# piccaloSchematic.net
KiCad netlist of a schematic drawn in Altium Designer
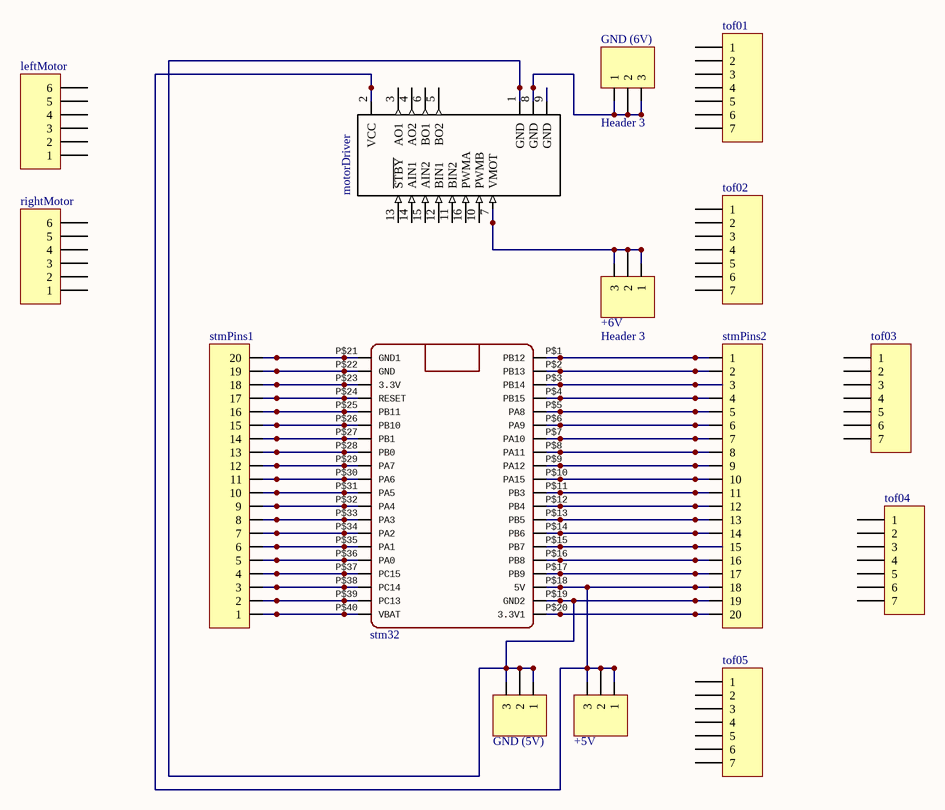
[diagram p0: piccaloSchematic.SchDoc]

(export (version "E")
  (design (tool "Eeschema 10.0.6"))
  (components
    (comp (ref "+5V")
      (value "Header 3")
      (footprint "HDR1X3")
      (description "Header, 3-Pin")
      (fields (field (name "PUBLISHER") "Altium Limited"))
      (libsource (lib "Miscellaneous Connectors") (part "Header 3"))
    )
    (comp (ref "+6V")
      (value "Header 3")
      (footprint "HDR1X3")
      (description "Header, 3-Pin")
      (fields (field (name "PUBLISHER") "Altium Limited"))
      (libsource (lib "Miscellaneous Connectors") (part "Header 3"))
    )
    (comp (ref "GND (5V)")
      (value "Header 3")
      (footprint "HDR1X3")
      (description "Header, 3-Pin")
      (fields (field (name "PUBLISHER") "Altium Limited"))
      (libsource (lib "Miscellaneous Connectors") (part "Header 3"))
    )
    (comp (ref "GND (6V)")
      (value "Header 3")
      (footprint "HDR1X3")
      (description "Header, 3-Pin")
      (fields (field (name "PUBLISHER") "Altium Limited"))
      (libsource (lib "") (part "Header 3_1"))
    )
    (comp (ref "leftMotor")
      (value "Header 6")
      (footprint "HDR1X6")
      (description "Header, 6-Pin")
      (fields (field (name "PUBLISHER") "Altium Limited"))
      (libsource (lib "Miscellaneous Connectors") (part "Header 6"))
    )
    (comp (ref "motorDriver")
      (value "POLOLU-713")
      (footprint "*SHIELD_POLOLU-713")
      (description "DC-motor driver; IC: TB6612FNG; 100kHz; 1A; Uin mot: 4.5")
      (fields (field (name "MF") "Pololu"))
      (libsource (lib "POLOLU-713") (part "POLOLU-713"))
    )
    (comp (ref "rightMotor")
      (value "Header 6")
      (footprint "HDR1X6")
      (description "Header, 6-Pin")
      (fields (field (name "PUBLISHER") "Altium Limited"))
      (libsource (lib "Miscellaneous Connectors") (part "Header 6"))
    )
    (comp (ref "stm32")
      (value "BLUE_PILLADVANCED")
      (footprint "BLUE_PILL_ADV")
      (libsource (lib "BluePill") (part "BLUE_PILLADVANCED"))
    )
    (comp (ref "stmPins1")
      (value "Header 20")
      (footprint "HDR1X20")
      (description "Header, 20-Pin")
      (fields (field (name "PUBLISHER") "Altium Limited"))
      (libsource (lib "") (part "Header 20_1"))
    )
    (comp (ref "stmPins2")
      (value "Header 20")
      (footprint "HDR1X20")
      (description "Header, 20-Pin")
      (fields (field (name "PUBLISHER") "Altium Limited"))
      (libsource (lib "Miscellaneous Connectors") (part "Header 20"))
    )
    (comp (ref "tof01")
      (value "Header 7")
      (footprint "HDR1X7")
      (description "Header, 7-Pin")
      (fields (field (name "PUBLISHER") "Altium Limited"))
      (libsource (lib "Miscellaneous Connectors") (part "Header 7"))
    )
    (comp (ref "tof02")
      (value "Header 7")
      (footprint "HDR1X7")
      (description "Header, 7-Pin")
      (fields (field (name "PUBLISHER") "Altium Limited"))
      (libsource (lib "Miscellaneous Connectors") (part "Header 7"))
    )
    (comp (ref "tof03")
      (value "Header 7")
      (footprint "HDR1X7")
      (description "Header, 7-Pin")
      (fields (field (name "PUBLISHER") "Altium Limited"))
      (libsource (lib "Miscellaneous Connectors") (part "Header 7"))
    )
    (comp (ref "tof04")
      (value "Header 7")
      (footprint "HDR1X7")
      (description "Header, 7-Pin")
      (fields (field (name "PUBLISHER") "Altium Limited"))
      (libsource (lib "Miscellaneous Connectors") (part "Header 7"))
    )
    (comp (ref "tof05")
      (value "Header 7")
      (footprint "HDR1X7")
      (description "Header, 7-Pin")
      (fields (field (name "PUBLISHER") "Altium Limited"))
      (libsource (lib "Miscellaneous Connectors") (part "Header 7"))
    )
  )
  (nets
    (net (code "1") (name "Net-(GND (6V)-Pad1)") (class "Default")
      (node (ref "GND (6V)") (pin "1") (pinfunction "1_1") (pintype "passive"))
      (node (ref "GND (6V)") (pin "2") (pinfunction "2_2") (pintype "passive"))
      (node (ref "GND (6V)") (pin "3") (pinfunction "3_3") (pintype "passive"))
      (node (ref "motorDriver") (pin "8") (pinfunction "GND_8") (pintype "power_in"))
    )
    (net (code "2") (name "Net-(motorDriver-VCC)") (class "Default")
      (node (ref "+5V") (pin "1") (pinfunction "1_1") (pintype "passive"))
      (node (ref "+5V") (pin "2") (pinfunction "2_2") (pintype "passive"))
      (node (ref "+5V") (pin "3") (pinfunction "3_3") (pintype "passive"))
      (node (ref "motorDriver") (pin "2") (pinfunction "VCC_2") (pintype "power_in"))
      (node (ref "stm32") (pin "P$18") (pinfunction "5V_P$18") (pintype "passive"))
      (node (ref "stmPins2") (pin "18") (pinfunction "18_18") (pintype "passive"))
    )
    (net (code "3") (name "Net-(motorDriver-VMOT)") (class "Default")
      (node (ref "+6V") (pin "1") (pinfunction "1_1") (pintype "passive"))
      (node (ref "+6V") (pin "2") (pinfunction "2_2") (pintype "passive"))
      (node (ref "+6V") (pin "3") (pinfunction "3_3") (pintype "passive"))
      (node (ref "motorDriver") (pin "7") (pinfunction "VMOT_7") (pintype "input"))
    )
    (net (code "4") (name "Net-(stm32-3.3V)") (class "Default")
      (node (ref "stm32") (pin "P$23") (pinfunction "3.3V_P$23") (pintype "passive"))
      (node (ref "stmPins1") (pin "18") (pinfunction "18_18") (pintype "passive"))
    )
    (net (code "5") (name "Net-(stm32-3.3V1)") (class "Default")
      (node (ref "stm32") (pin "P$20") (pinfunction "3.3V1_P$20") (pintype "passive"))
      (node (ref "stmPins2") (pin "20") (pinfunction "20_20") (pintype "passive"))
    )
    (net (code "6") (name "Net-(stm32-GND)") (class "Default")
      (node (ref "stm32") (pin "P$22") (pinfunction "GND_P$22") (pintype "passive"))
      (node (ref "stmPins1") (pin "19") (pinfunction "19_19") (pintype "passive"))
    )
    (net (code "7") (name "Net-(stm32-GND1)") (class "Default")
      (node (ref "stm32") (pin "P$21") (pinfunction "GND1_P$21") (pintype "power_in"))
      (node (ref "stmPins1") (pin "20") (pinfunction "20_20") (pintype "passive"))
    )
    (net (code "8") (name "Net-(stm32-GND2)") (class "Default")
      (node (ref "GND (5V)") (pin "1") (pinfunction "1_1") (pintype "passive"))
      (node (ref "GND (5V)") (pin "2") (pinfunction "2_2") (pintype "passive"))
      (node (ref "GND (5V)") (pin "3") (pinfunction "3_3") (pintype "passive"))
      (node (ref "motorDriver") (pin "1") (pinfunction "GND_1") (pintype "power_in"))
      (node (ref "stm32") (pin "P$19") (pinfunction "GND2_P$19") (pintype "passive"))
      (node (ref "stmPins2") (pin "19") (pinfunction "19_19") (pintype "passive"))
    )
    (net (code "9") (name "Net-(stm32-PA0)") (class "Default")
      (node (ref "stm32") (pin "P$36") (pinfunction "PA0_P$36") (pintype "passive"))
      (node (ref "stmPins1") (pin "5") (pinfunction "5_5") (pintype "passive"))
    )
    (net (code "10") (name "Net-(stm32-PA1)") (class "Default")
      (node (ref "stm32") (pin "P$35") (pinfunction "PA1_P$35") (pintype "passive"))
      (node (ref "stmPins1") (pin "6") (pinfunction "6_6") (pintype "passive"))
    )
    (net (code "11") (name "Net-(stm32-PA2)") (class "Default")
      (node (ref "stm32") (pin "P$34") (pinfunction "PA2_P$34") (pintype "passive"))
      (node (ref "stmPins1") (pin "7") (pinfunction "7_7") (pintype "passive"))
    )
    (net (code "12") (name "Net-(stm32-PA3)") (class "Default")
      (node (ref "stm32") (pin "P$33") (pinfunction "PA3_P$33") (pintype "passive"))
      (node (ref "stmPins1") (pin "8") (pinfunction "8_8") (pintype "passive"))
    )
    (net (code "13") (name "Net-(stm32-PA4)") (class "Default")
      (node (ref "stm32") (pin "P$32") (pinfunction "PA4_P$32") (pintype "passive"))
      (node (ref "stmPins1") (pin "9") (pinfunction "9_9") (pintype "passive"))
    )
    (net (code "14") (name "Net-(stm32-PA5)") (class "Default")
      (node (ref "stm32") (pin "P$31") (pinfunction "PA5_P$31") (pintype "passive"))
      (node (ref "stmPins1") (pin "10") (pinfunction "10_10") (pintype "passive"))
    )
    (net (code "15") (name "Net-(stm32-PA6)") (class "Default")
      (node (ref "stm32") (pin "P$30") (pinfunction "PA6_P$30") (pintype "passive"))
      (node (ref "stmPins1") (pin "11") (pinfunction "11_11") (pintype "passive"))
    )
    (net (code "16") (name "Net-(stm32-PA7)") (class "Default")
      (node (ref "stm32") (pin "P$29") (pinfunction "PA7_P$29") (pintype "passive"))
      (node (ref "stmPins1") (pin "12") (pinfunction "12_12") (pintype "passive"))
    )
    (net (code "17") (name "Net-(stm32-PA8)") (class "Default")
      (node (ref "stm32") (pin "P$5") (pinfunction "PA8_P$5") (pintype "passive"))
      (node (ref "stmPins2") (pin "5") (pinfunction "5_5") (pintype "passive"))
    )
    (net (code "18") (name "Net-(stm32-PA9)") (class "Default")
      (node (ref "stm32") (pin "P$6") (pinfunction "PA9_P$6") (pintype "passive"))
      (node (ref "stmPins2") (pin "6") (pinfunction "6_6") (pintype "passive"))
    )
    (net (code "19") (name "Net-(stm32-PA10)") (class "Default")
      (node (ref "stm32") (pin "P$7") (pinfunction "PA10_P$7") (pintype "passive"))
      (node (ref "stmPins2") (pin "7") (pinfunction "7_7") (pintype "passive"))
    )
    (net (code "20") (name "Net-(stm32-PA11)") (class "Default")
      (node (ref "stm32") (pin "P$8") (pinfunction "PA11_P$8") (pintype "passive"))
      (node (ref "stmPins2") (pin "8") (pinfunction "8_8") (pintype "passive"))
    )
    (net (code "21") (name "Net-(stm32-PA12)") (class "Default")
      (node (ref "stm32") (pin "P$9") (pinfunction "PA12_P$9") (pintype "passive"))
      (node (ref "stmPins2") (pin "9") (pinfunction "9_9") (pintype "passive"))
    )
    (net (code "22") (name "Net-(stm32-PA15)") (class "Default")
      (node (ref "stm32") (pin "P$10") (pinfunction "PA15_P$10") (pintype "passive"))
      (node (ref "stmPins2") (pin "10") (pinfunction "10_10") (pintype "passive"))
    )
    (net (code "23") (name "Net-(stm32-PB0)") (class "Default")
      (node (ref "stm32") (pin "P$28") (pinfunction "PB0_P$28") (pintype "passive"))
      (node (ref "stmPins1") (pin "13") (pinfunction "13_13") (pintype "passive"))
    )
    (net (code "24") (name "Net-(stm32-PB1)") (class "Default")
      (node (ref "stm32") (pin "P$27") (pinfunction "PB1_P$27") (pintype "passive"))
      (node (ref "stmPins1") (pin "14") (pinfunction "14_14") (pintype "passive"))
    )
    (net (code "25") (name "Net-(stm32-PB3)") (class "Default")
      (node (ref "stm32") (pin "P$11") (pinfunction "PB3_P$11") (pintype "passive"))
      (node (ref "stmPins2") (pin "11") (pinfunction "11_11") (pintype "passive"))
    )
    (net (code "26") (name "Net-(stm32-PB4)") (class "Default")
      (node (ref "stm32") (pin "P$12") (pinfunction "PB4_P$12") (pintype "passive"))
      (node (ref "stmPins2") (pin "12") (pinfunction "12_12") (pintype "passive"))
    )
    (net (code "27") (name "Net-(stm32-PB5)") (class "Default")
      (node (ref "stm32") (pin "P$13") (pinfunction "PB5_P$13") (pintype "passive"))
      (node (ref "stmPins2") (pin "13") (pinfunction "13_13") (pintype "passive"))
    )
    (net (code "28") (name "Net-(stm32-PB6)") (class "Default")
      (node (ref "stm32") (pin "P$14") (pinfunction "PB6_P$14") (pintype "passive"))
      (node (ref "stmPins2") (pin "14") (pinfunction "14_14") (pintype "passive"))
    )
    (net (code "29") (name "Net-(stm32-PB7)") (class "Default")
      (node (ref "stm32") (pin "P$15") (pinfunction "PB7_P$15") (pintype "passive"))
      (node (ref "stmPins2") (pin "15") (pinfunction "15_15") (pintype "passive"))
    )
    (net (code "30") (name "Net-(stm32-PB8)") (class "Default")
      (node (ref "stm32") (pin "P$16") (pinfunction "PB8_P$16") (pintype "passive"))
      (node (ref "stmPins2") (pin "16") (pinfunction "16_16") (pintype "passive"))
    )
    (net (code "31") (name "Net-(stm32-PB9)") (class "Default")
      (node (ref "stm32") (pin "P$17") (pinfunction "PB9_P$17") (pintype "passive"))
      (node (ref "stmPins2") (pin "17") (pinfunction "17_17") (pintype "passive"))
    )
    (net (code "32") (name "Net-(stm32-PB10)") (class "Default")
      (node (ref "stm32") (pin "P$26") (pinfunction "PB10_P$26") (pintype "passive"))
      (node (ref "stmPins1") (pin "15") (pinfunction "15_15") (pintype "passive"))
    )
    (net (code "33") (name "Net-(stm32-PB11)") (class "Default")
      (node (ref "stm32") (pin "P$25") (pinfunction "PB11_P$25") (pintype "passive"))
      (node (ref "stmPins1") (pin "16") (pinfunction "16_16") (pintype "passive"))
    )
    (net (code "34") (name "Net-(stm32-PB12)") (class "Default")
      (node (ref "stm32") (pin "P$1") (pinfunction "PB12_P$1") (pintype "passive"))
      (node (ref "stmPins2") (pin "1") (pinfunction "1_1") (pintype "passive"))
    )
    (net (code "35") (name "Net-(stm32-PB13)") (class "Default")
      (node (ref "stm32") (pin "P$2") (pinfunction "PB13_P$2") (pintype "passive"))
      (node (ref "stmPins2") (pin "2") (pinfunction "2_2") (pintype "passive"))
    )
    (net (code "36") (name "Net-(stm32-PB14)") (class "Default")
      (node (ref "stm32") (pin "P$3") (pinfunction "PB14_P$3") (pintype "passive"))
      (node (ref "stmPins2") (pin "3") (pinfunction "3_3") (pintype "passive"))
    )
    (net (code "37") (name "Net-(stm32-PB15)") (class "Default")
      (node (ref "stm32") (pin "P$4") (pinfunction "PB15_P$4") (pintype "passive"))
      (node (ref "stmPins2") (pin "4") (pinfunction "4_4") (pintype "passive"))
    )
    (net (code "38") (name "Net-(stm32-PC13)") (class "Default")
      (node (ref "stm32") (pin "P$39") (pinfunction "PC13_P$39") (pintype "passive"))
      (node (ref "stmPins1") (pin "2") (pinfunction "2_2") (pintype "passive"))
    )
    (net (code "39") (name "Net-(stm32-PC14)") (class "Default")
      (node (ref "stm32") (pin "P$38") (pinfunction "PC14_P$38") (pintype "passive"))
      (node (ref "stmPins1") (pin "3") (pinfunction "3_3") (pintype "passive"))
    )
    (net (code "40") (name "Net-(stm32-PC15)") (class "Default")
      (node (ref "stm32") (pin "P$37") (pinfunction "PC15_P$37") (pintype "passive"))
      (node (ref "stmPins1") (pin "4") (pinfunction "4_4") (pintype "passive"))
    )
    (net (code "41") (name "Net-(stm32-RESET)") (class "Default")
      (node (ref "stm32") (pin "P$24") (pinfunction "RESET_P$24") (pintype "passive"))
      (node (ref "stmPins1") (pin "17") (pinfunction "17_17") (pintype "passive"))
    )
    (net (code "42") (name "Net-(stm32-VBAT)") (class "Default")
      (node (ref "stm32") (pin "P$40") (pinfunction "VBAT_P$40") (pintype "passive"))
      (node (ref "stmPins1") (pin "1") (pinfunction "1_1") (pintype "passive"))
    )
    (net (code "43") (name "unconnected-(leftMotor-Pad1)") (class "Default")
      (node (ref "leftMotor") (pin "1") (pinfunction "1_1") (pintype "passive"))
    )
    (net (code "44") (name "unconnected-(leftMotor-Pad2)") (class "Default")
      (node (ref "leftMotor") (pin "2") (pinfunction "2_2") (pintype "passive"))
    )
    (net (code "45") (name "unconnected-(leftMotor-Pad3)") (class "Default")
      (node (ref "leftMotor") (pin "3") (pinfunction "3_3") (pintype "passive"))
    )
    (net (code "46") (name "unconnected-(leftMotor-Pad4)") (class "Default")
      (node (ref "leftMotor") (pin "4") (pinfunction "4_4") (pintype "passive"))
    )
    (net (code "47") (name "unconnected-(leftMotor-Pad5)") (class "Default")
      (node (ref "leftMotor") (pin "5") (pinfunction "5_5") (pintype "passive"))
    )
    (net (code "48") (name "unconnected-(leftMotor-Pad6)") (class "Default")
      (node (ref "leftMotor") (pin "6") (pinfunction "6_6") (pintype "passive"))
    )
    (net (code "49") (name "unconnected-(motorDriver-AIN1-Pad14)") (class "Default")
      (node (ref "motorDriver") (pin "14") (pinfunction "AIN1_14") (pintype "input"))
    )
    (net (code "50") (name "unconnected-(motorDriver-AIN2-Pad15)") (class "Default")
      (node (ref "motorDriver") (pin "15") (pinfunction "AIN2_15") (pintype "input"))
    )
    (net (code "51") (name "unconnected-(motorDriver-AO1-Pad3)") (class "Default")
      (node (ref "motorDriver") (pin "3") (pinfunction "AO1_3") (pintype "output"))
    )
    (net (code "52") (name "unconnected-(motorDriver-AO2-Pad4)") (class "Default")
      (node (ref "motorDriver") (pin "4") (pinfunction "AO2_4") (pintype "output"))
    )
    (net (code "53") (name "unconnected-(motorDriver-BIN1-Pad12)") (class "Default")
      (node (ref "motorDriver") (pin "12") (pinfunction "BIN1_12") (pintype "input"))
    )
    (net (code "54") (name "unconnected-(motorDriver-BIN2-Pad11)") (class "Default")
      (node (ref "motorDriver") (pin "11") (pinfunction "BIN2_11") (pintype "input"))
    )
    (net (code "55") (name "unconnected-(motorDriver-BO1-Pad6)") (class "Default")
      (node (ref "motorDriver") (pin "6") (pinfunction "BO1_6") (pintype "output"))
    )
    (net (code "56") (name "unconnected-(motorDriver-BO2-Pad5)") (class "Default")
      (node (ref "motorDriver") (pin "5") (pinfunction "BO2_5") (pintype "output"))
    )
    (net (code "57") (name "unconnected-(motorDriver-GND-Pad9)") (class "Default")
      (node (ref "motorDriver") (pin "9") (pinfunction "GND_9") (pintype "power_in"))
    )
    (net (code "58") (name "unconnected-(motorDriver-PWMA-Pad16)") (class "Default")
      (node (ref "motorDriver") (pin "16") (pinfunction "PWMA_16") (pintype "input"))
    )
    (net (code "59") (name "unconnected-(motorDriver-PWMB-Pad10)") (class "Default")
      (node (ref "motorDriver") (pin "10") (pinfunction "PWMB_10") (pintype "input"))
    )
    (net (code "60") (name "unconnected-(motorDriver-~{STBY}-Pad13)") (class "Default")
      (node (ref "motorDriver") (pin "13") (pinfunction "~{STBY}_13") (pintype "input"))
    )
    (net (code "61") (name "unconnected-(rightMotor-Pad1)") (class "Default")
      (node (ref "rightMotor") (pin "1") (pinfunction "1_1") (pintype "passive"))
    )
    (net (code "62") (name "unconnected-(rightMotor-Pad2)") (class "Default")
      (node (ref "rightMotor") (pin "2") (pinfunction "2_2") (pintype "passive"))
    )
    (net (code "63") (name "unconnected-(rightMotor-Pad3)") (class "Default")
      (node (ref "rightMotor") (pin "3") (pinfunction "3_3") (pintype "passive"))
    )
    (net (code "64") (name "unconnected-(rightMotor-Pad4)") (class "Default")
      (node (ref "rightMotor") (pin "4") (pinfunction "4_4") (pintype "passive"))
    )
    (net (code "65") (name "unconnected-(rightMotor-Pad5)") (class "Default")
      (node (ref "rightMotor") (pin "5") (pinfunction "5_5") (pintype "passive"))
    )
    (net (code "66") (name "unconnected-(rightMotor-Pad6)") (class "Default")
      (node (ref "rightMotor") (pin "6") (pinfunction "6_6") (pintype "passive"))
    )
    (net (code "67") (name "unconnected-(tof01-Pad1)") (class "Default")
      (node (ref "tof01") (pin "1") (pinfunction "1_1") (pintype "passive"))
    )
    (net (code "68") (name "unconnected-(tof01-Pad2)") (class "Default")
      (node (ref "tof01") (pin "2") (pinfunction "2_2") (pintype "passive"))
    )
    (net (code "69") (name "unconnected-(tof01-Pad3)") (class "Default")
      (node (ref "tof01") (pin "3") (pinfunction "3_3") (pintype "passive"))
    )
    (net (code "70") (name "unconnected-(tof01-Pad4)") (class "Default")
      (node (ref "tof01") (pin "4") (pinfunction "4_4") (pintype "passive"))
    )
    (net (code "71") (name "unconnected-(tof01-Pad5)") (class "Default")
      (node (ref "tof01") (pin "5") (pinfunction "5_5") (pintype "passive"))
    )
    (net (code "72") (name "unconnected-(tof01-Pad6)") (class "Default")
      (node (ref "tof01") (pin "6") (pinfunction "6_6") (pintype "passive"))
    )
    (net (code "73") (name "unconnected-(tof01-Pad7)") (class "Default")
      (node (ref "tof01") (pin "7") (pinfunction "7_7") (pintype "passive"))
    )
    (net (code "74") (name "unconnected-(tof02-Pad1)") (class "Default")
      (node (ref "tof02") (pin "1") (pinfunction "1_1") (pintype "passive"))
    )
    (net (code "75") (name "unconnected-(tof02-Pad2)") (class "Default")
      (node (ref "tof02") (pin "2") (pinfunction "2_2") (pintype "passive"))
    )
    (net (code "76") (name "unconnected-(tof02-Pad3)") (class "Default")
      (node (ref "tof02") (pin "3") (pinfunction "3_3") (pintype "passive"))
    )
    (net (code "77") (name "unconnected-(tof02-Pad4)") (class "Default")
      (node (ref "tof02") (pin "4") (pinfunction "4_4") (pintype "passive"))
    )
    (net (code "78") (name "unconnected-(tof02-Pad5)") (class "Default")
      (node (ref "tof02") (pin "5") (pinfunction "5_5") (pintype "passive"))
    )
    (net (code "79") (name "unconnected-(tof02-Pad6)") (class "Default")
      (node (ref "tof02") (pin "6") (pinfunction "6_6") (pintype "passive"))
    )
    (net (code "80") (name "unconnected-(tof02-Pad7)") (class "Default")
      (node (ref "tof02") (pin "7") (pinfunction "7_7") (pintype "passive"))
    )
    (net (code "81") (name "unconnected-(tof03-Pad1)") (class "Default")
      (node (ref "tof03") (pin "1") (pinfunction "1_1") (pintype "passive"))
    )
    (net (code "82") (name "unconnected-(tof03-Pad2)") (class "Default")
      (node (ref "tof03") (pin "2") (pinfunction "2_2") (pintype "passive"))
    )
    (net (code "83") (name "unconnected-(tof03-Pad3)") (class "Default")
      (node (ref "tof03") (pin "3") (pinfunction "3_3") (pintype "passive"))
    )
    (net (code "84") (name "unconnected-(tof03-Pad4)") (class "Default")
      (node (ref "tof03") (pin "4") (pinfunction "4_4") (pintype "passive"))
    )
    (net (code "85") (name "unconnected-(tof03-Pad5)") (class "Default")
      (node (ref "tof03") (pin "5") (pinfunction "5_5") (pintype "passive"))
    )
    (net (code "86") (name "unconnected-(tof03-Pad6)") (class "Default")
      (node (ref "tof03") (pin "6") (pinfunction "6_6") (pintype "passive"))
    )
    (net (code "87") (name "unconnected-(tof03-Pad7)") (class "Default")
      (node (ref "tof03") (pin "7") (pinfunction "7_7") (pintype "passive"))
    )
    (net (code "88") (name "unconnected-(tof04-Pad1)") (class "Default")
      (node (ref "tof04") (pin "1") (pinfunction "1_1") (pintype "passive"))
    )
    (net (code "89") (name "unconnected-(tof04-Pad2)") (class "Default")
      (node (ref "tof04") (pin "2") (pinfunction "2_2") (pintype "passive"))
    )
    (net (code "90") (name "unconnected-(tof04-Pad3)") (class "Default")
      (node (ref "tof04") (pin "3") (pinfunction "3_3") (pintype "passive"))
    )
    (net (code "91") (name "unconnected-(tof04-Pad4)") (class "Default")
      (node (ref "tof04") (pin "4") (pinfunction "4_4") (pintype "passive"))
    )
    (net (code "92") (name "unconnected-(tof04-Pad5)") (class "Default")
      (node (ref "tof04") (pin "5") (pinfunction "5_5") (pintype "passive"))
    )
    (net (code "93") (name "unconnected-(tof04-Pad6)") (class "Default")
      (node (ref "tof04") (pin "6") (pinfunction "6_6") (pintype "passive"))
    )
    (net (code "94") (name "unconnected-(tof04-Pad7)") (class "Default")
      (node (ref "tof04") (pin "7") (pinfunction "7_7") (pintype "passive"))
    )
    (net (code "95") (name "unconnected-(tof05-Pad1)") (class "Default")
      (node (ref "tof05") (pin "1") (pinfunction "1_1") (pintype "passive"))
    )
    (net (code "96") (name "unconnected-(tof05-Pad2)") (class "Default")
      (node (ref "tof05") (pin "2") (pinfunction "2_2") (pintype "passive"))
    )
    (net (code "97") (name "unconnected-(tof05-Pad3)") (class "Default")
      (node (ref "tof05") (pin "3") (pinfunction "3_3") (pintype "passive"))
    )
    (net (code "98") (name "unconnected-(tof05-Pad4)") (class "Default")
      (node (ref "tof05") (pin "4") (pinfunction "4_4") (pintype "passive"))
    )
    (net (code "99") (name "unconnected-(tof05-Pad5)") (class "Default")
      (node (ref "tof05") (pin "5") (pinfunction "5_5") (pintype "passive"))
    )
    (net (code "100") (name "unconnected-(tof05-Pad6)") (class "Default")
      (node (ref "tof05") (pin "6") (pinfunction "6_6") (pintype "passive"))
    )
    (net (code "101") (name "unconnected-(tof05-Pad7)") (class "Default")
      (node (ref "tof05") (pin "7") (pinfunction "7_7") (pintype "passive"))
    )
  )
)
